# main.net
KiCad netlist of a schematic drawn in Altium Designer
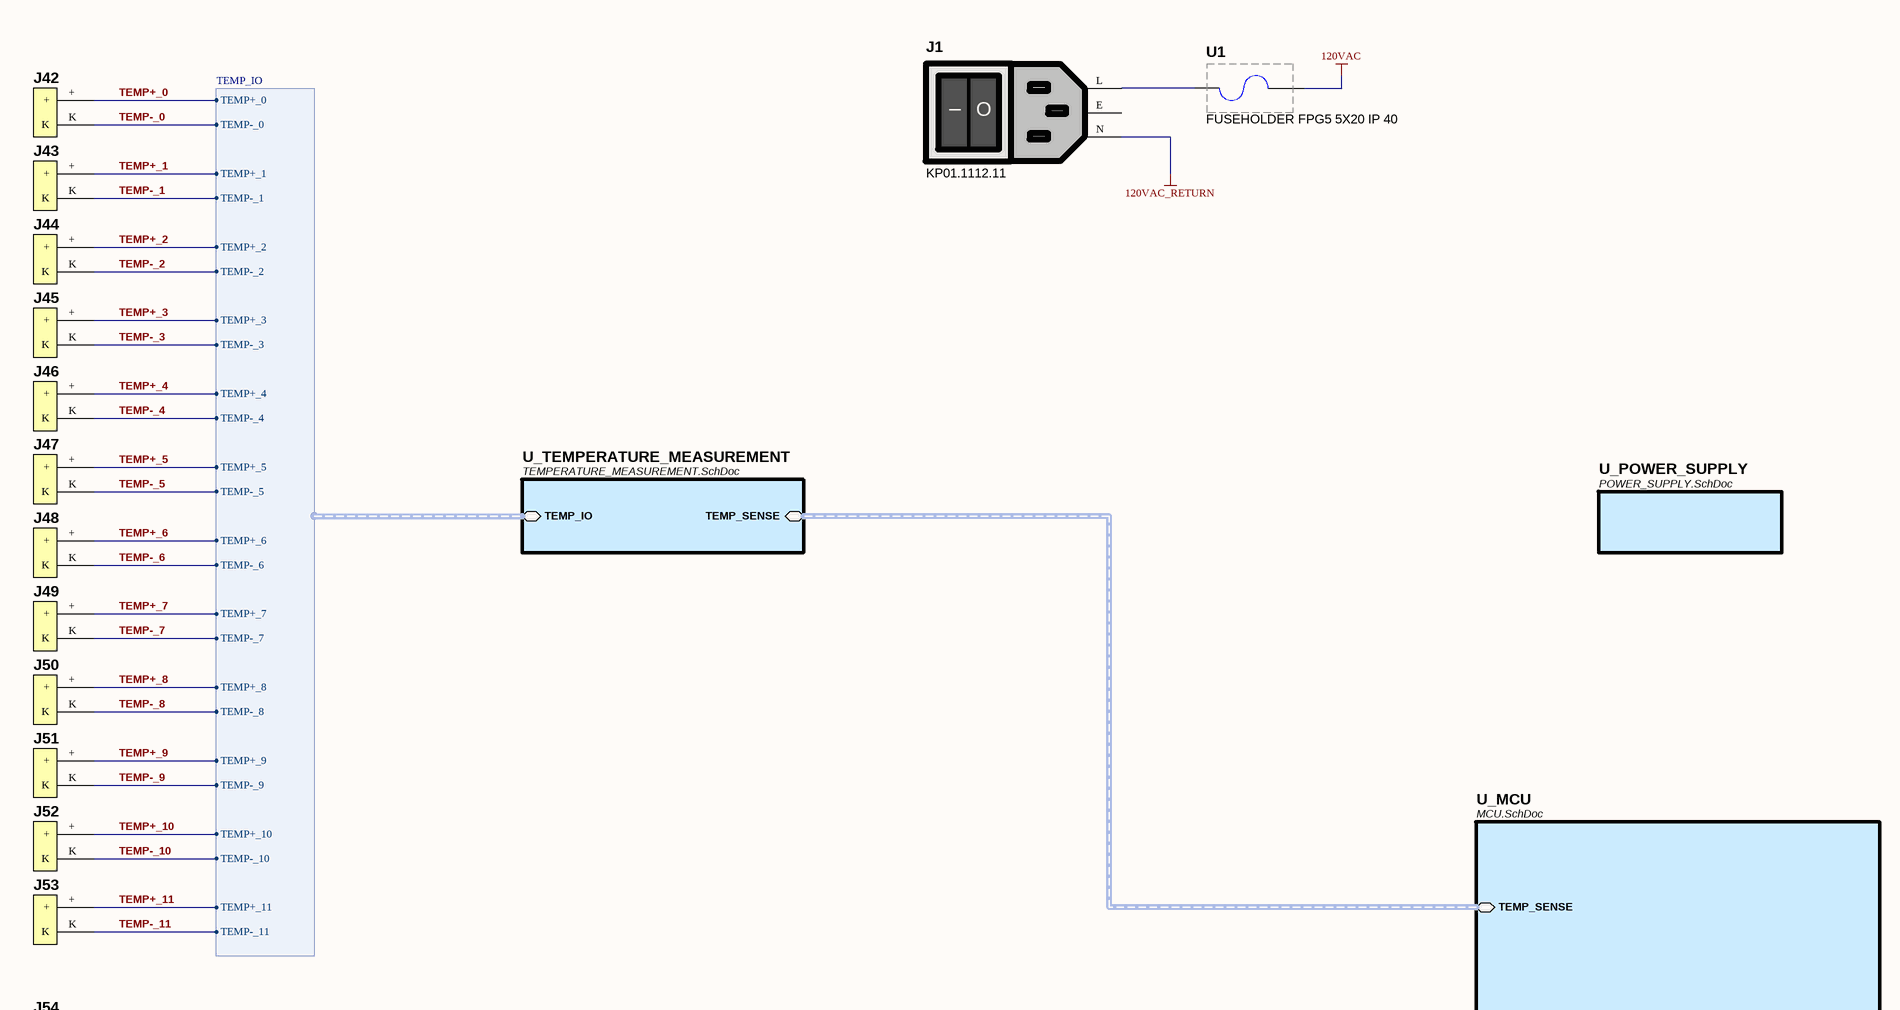
[diagram p0: main.SchDoc, top left]
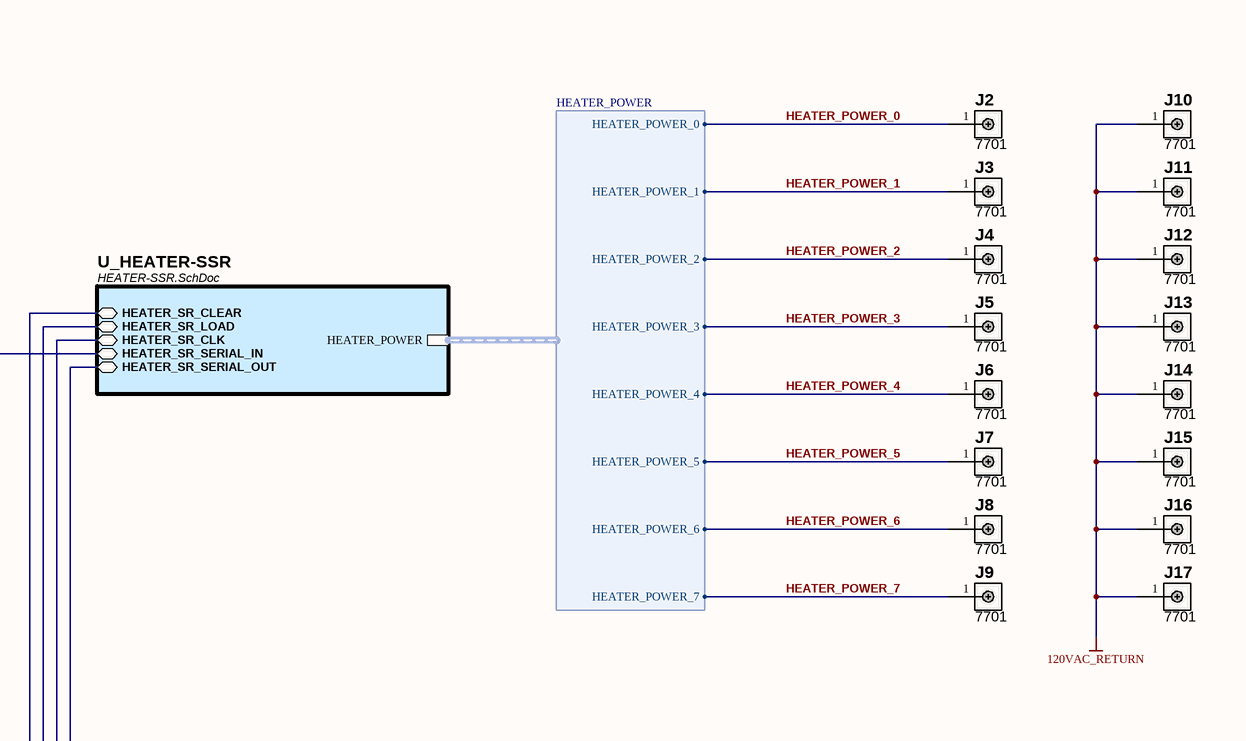
[diagram p1: main.SchDoc, top right]
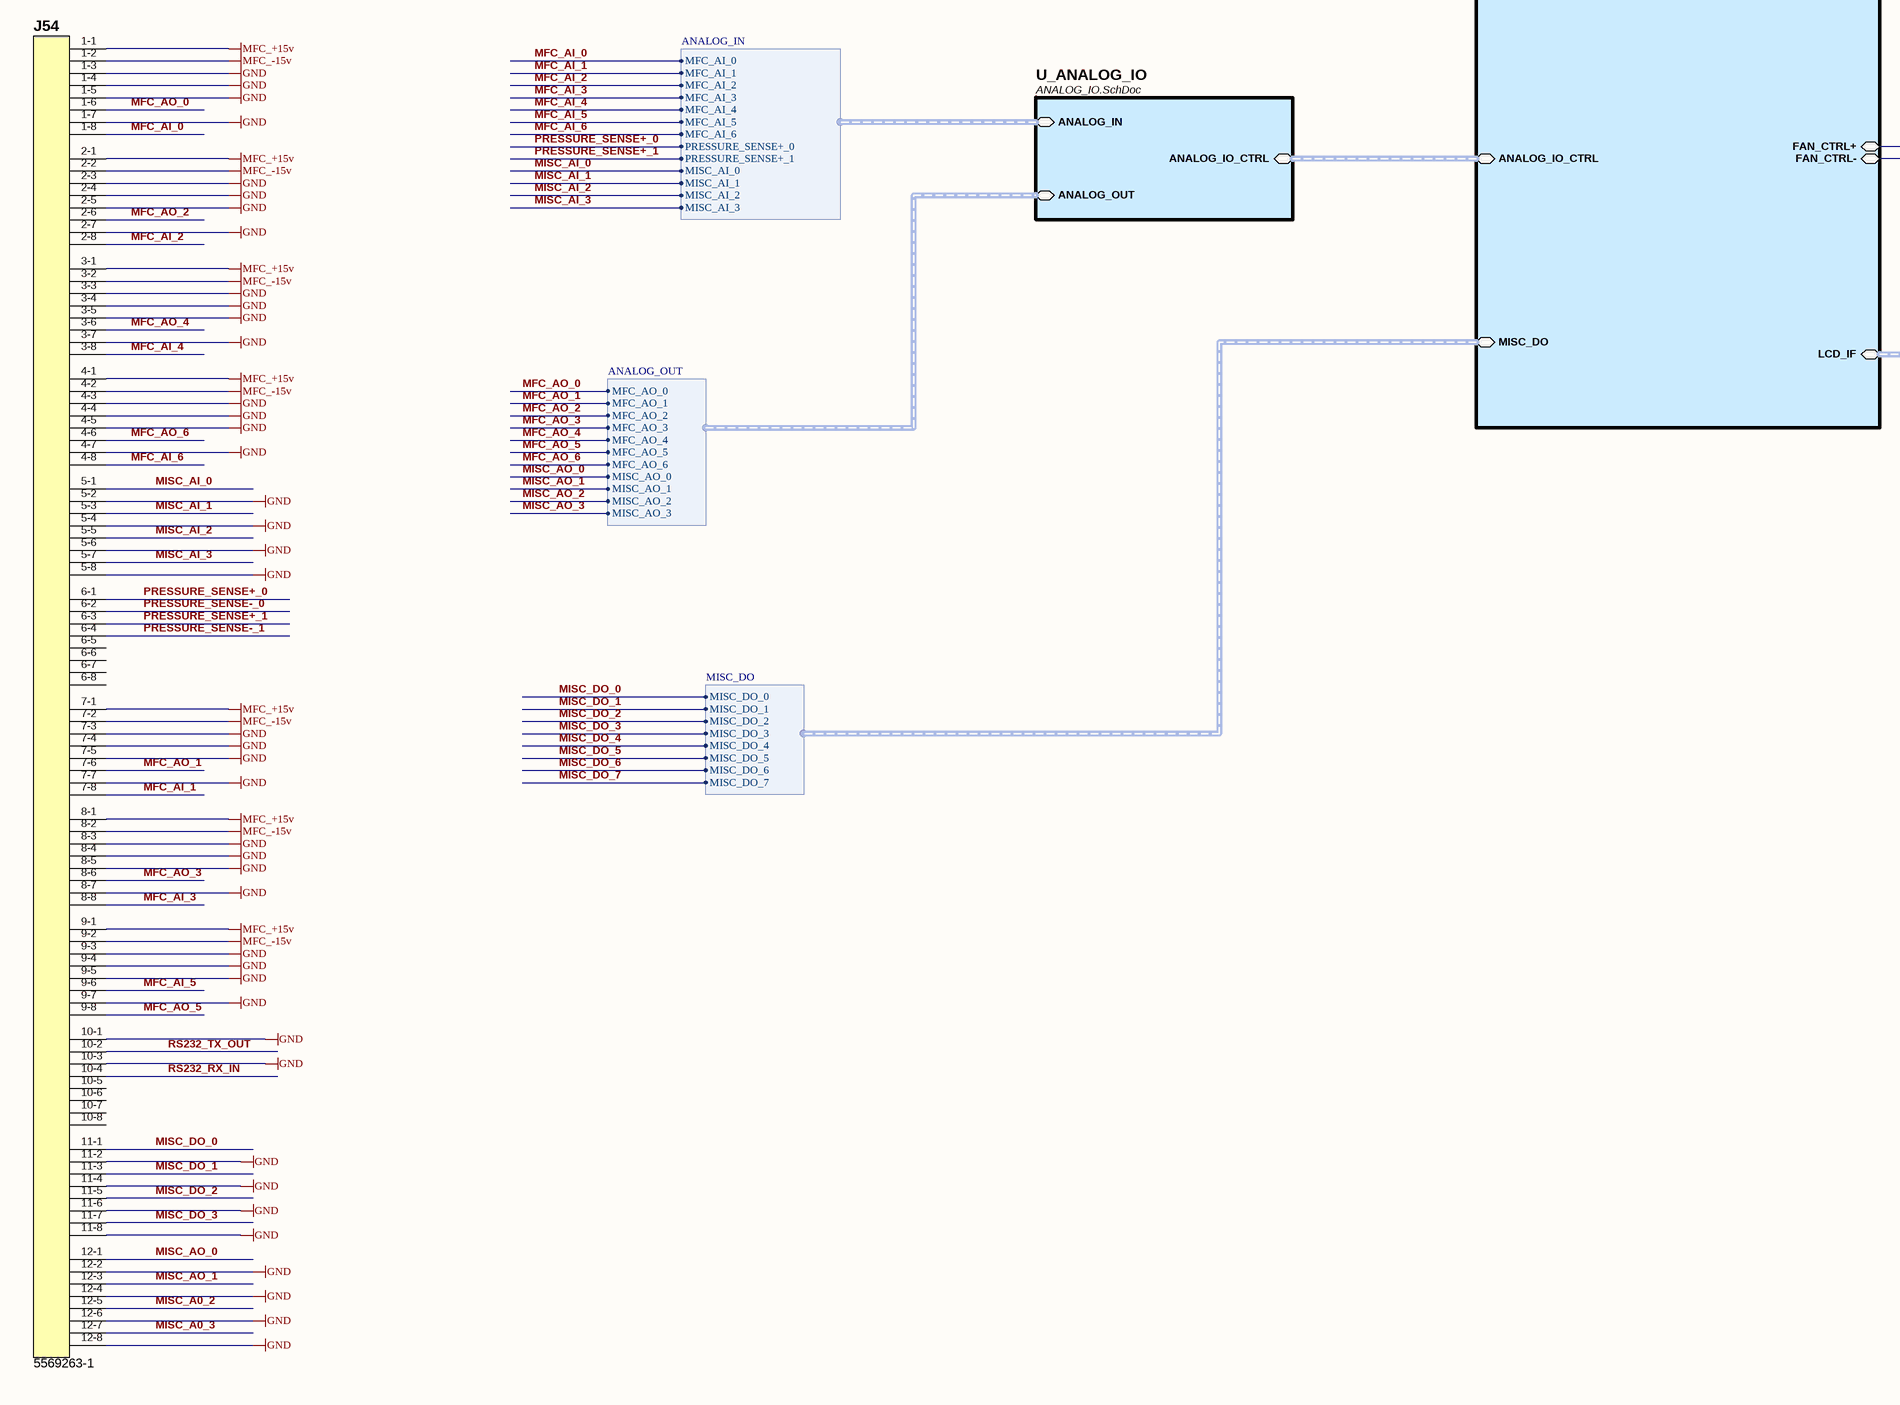
[diagram p2: main.SchDoc, bottom left]
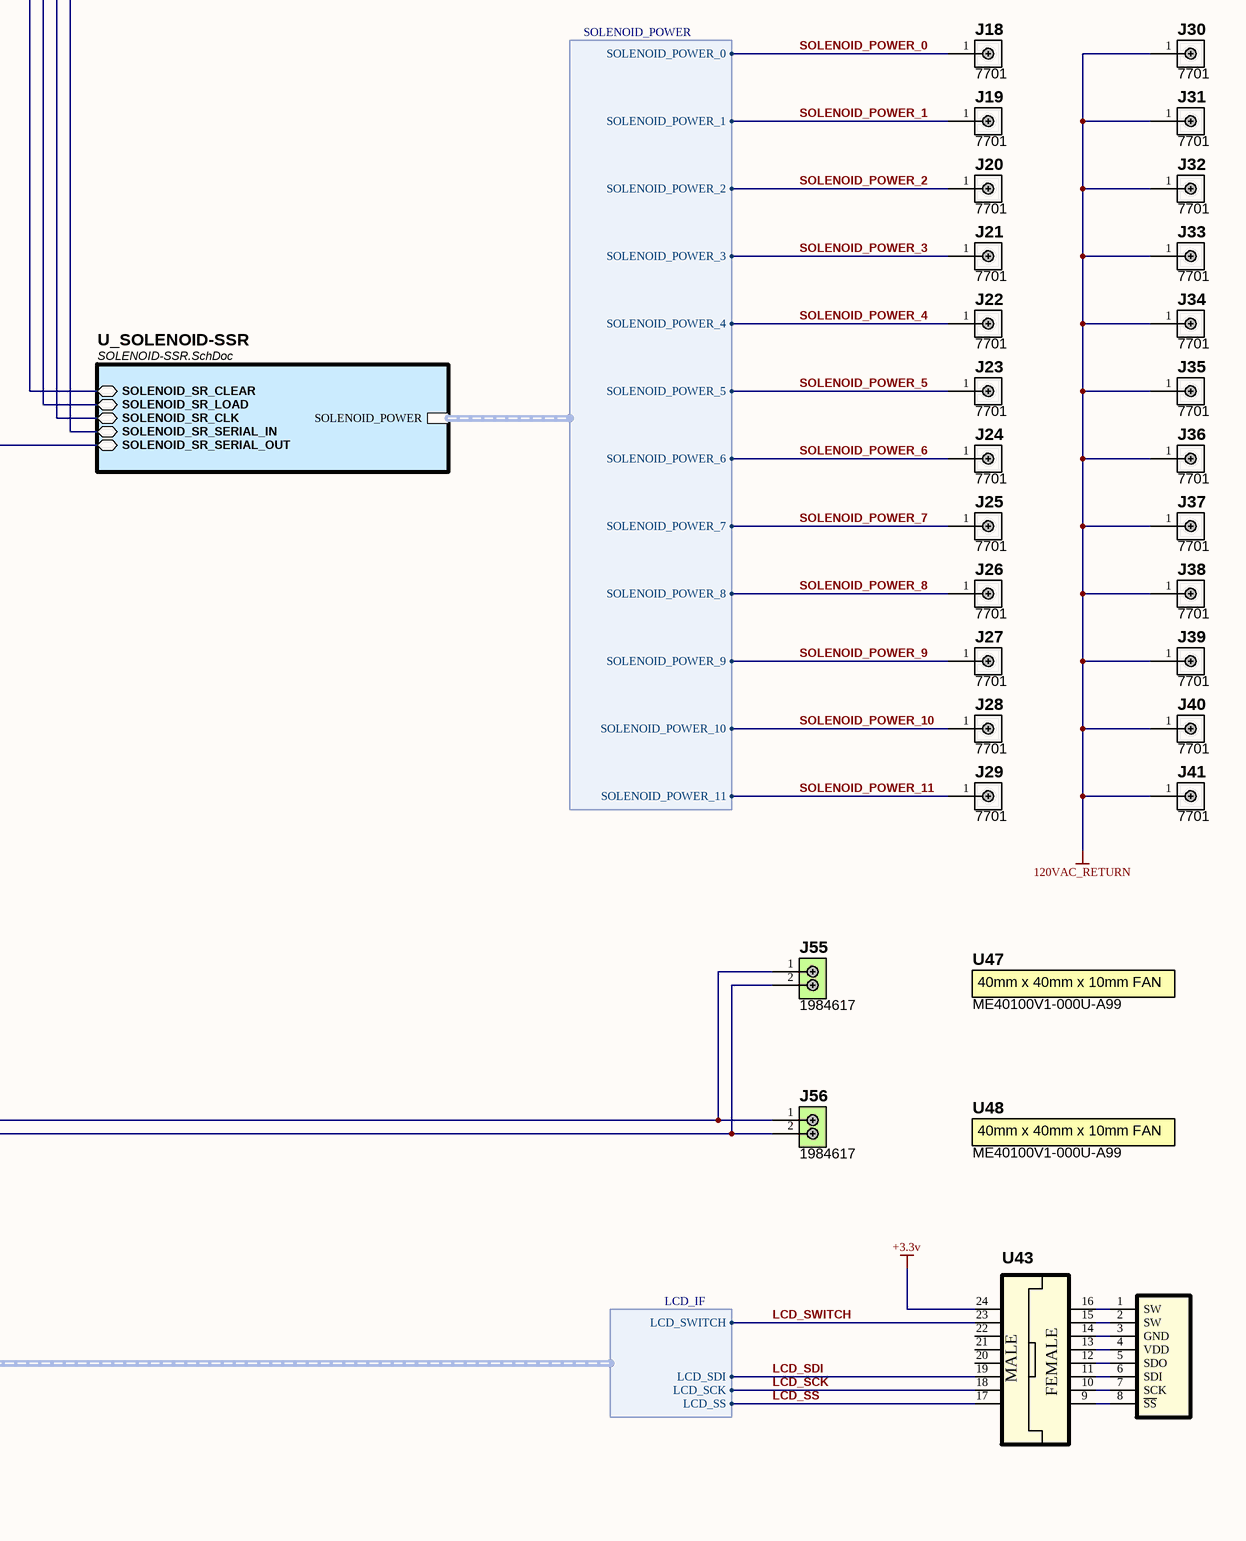
[diagram p3: main.SchDoc, bottom right]

(export (version "E")
  (design (tool "Eeschema 10.0.6"))
  (components
    (comp (ref "J1")
      (value "KP01.1112.11")
      (footprint "KP01.1112.11")
      (description "AC Power Entry Modules SNAP-N PCB 2-POLE")
      (fields (field (name "MANUFACTURER") "Schurter"))
      (libsource (lib "eModule") (part "KP01.1112.11"))
    )
    (comp (ref "J2")
      (value "7701")
      (footprint "7701")
      (description "TERM W/ASSEMBLD SCREW VERT PCMNT")
      (fields (field (name "MANUFACTURER") "Keystone Electronics"))
      (libsource (lib "eConnector") (part "7701"))
    )
    (comp (ref "J3")
      (value "7701")
      (footprint "7701")
      (description "TERM W/ASSEMBLD SCREW VERT PCMNT")
      (fields (field (name "MANUFACTURER") "Keystone Electronics"))
      (libsource (lib "eConnector") (part "7701"))
    )
    (comp (ref "J4")
      (value "7701")
      (footprint "7701")
      (description "TERM W/ASSEMBLD SCREW VERT PCMNT")
      (fields (field (name "MANUFACTURER") "Keystone Electronics"))
      (libsource (lib "eConnector") (part "7701"))
    )
    (comp (ref "J5")
      (value "7701")
      (footprint "7701")
      (description "TERM W/ASSEMBLD SCREW VERT PCMNT")
      (fields (field (name "MANUFACTURER") "Keystone Electronics"))
      (libsource (lib "eConnector") (part "7701"))
    )
    (comp (ref "J6")
      (value "7701")
      (footprint "7701")
      (description "TERM W/ASSEMBLD SCREW VERT PCMNT")
      (fields (field (name "MANUFACTURER") "Keystone Electronics"))
      (libsource (lib "eConnector") (part "7701"))
    )
    (comp (ref "J7")
      (value "7701")
      (footprint "7701")
      (description "TERM W/ASSEMBLD SCREW VERT PCMNT")
      (fields (field (name "MANUFACTURER") "Keystone Electronics"))
      (libsource (lib "eConnector") (part "7701"))
    )
    (comp (ref "J8")
      (value "7701")
      (footprint "7701")
      (description "TERM W/ASSEMBLD SCREW VERT PCMNT")
      (fields (field (name "MANUFACTURER") "Keystone Electronics"))
      (libsource (lib "eConnector") (part "7701"))
    )
    (comp (ref "J9")
      (value "7701")
      (footprint "7701")
      (description "TERM W/ASSEMBLD SCREW VERT PCMNT")
      (fields (field (name "MANUFACTURER") "Keystone Electronics"))
      (libsource (lib "eConnector") (part "7701"))
    )
    (comp (ref "J10")
      (value "7701")
      (footprint "7701")
      (description "TERM W/ASSEMBLD SCREW VERT PCMNT")
      (fields (field (name "MANUFACTURER") "Keystone Electronics"))
      (libsource (lib "eConnector") (part "7701"))
    )
    (comp (ref "J11")
      (value "7701")
      (footprint "7701")
      (description "TERM W/ASSEMBLD SCREW VERT PCMNT")
      (fields (field (name "MANUFACTURER") "Keystone Electronics"))
      (libsource (lib "eConnector") (part "7701"))
    )
    (comp (ref "J12")
      (value "7701")
      (footprint "7701")
      (description "TERM W/ASSEMBLD SCREW VERT PCMNT")
      (fields (field (name "MANUFACTURER") "Keystone Electronics"))
      (libsource (lib "eConnector") (part "7701"))
    )
    (comp (ref "J13")
      (value "7701")
      (footprint "7701")
      (description "TERM W/ASSEMBLD SCREW VERT PCMNT")
      (fields (field (name "MANUFACTURER") "Keystone Electronics"))
      (libsource (lib "eConnector") (part "7701"))
    )
    (comp (ref "J14")
      (value "7701")
      (footprint "7701")
      (description "TERM W/ASSEMBLD SCREW VERT PCMNT")
      (fields (field (name "MANUFACTURER") "Keystone Electronics"))
      (libsource (lib "eConnector") (part "7701"))
    )
    (comp (ref "J15")
      (value "7701")
      (footprint "7701")
      (description "TERM W/ASSEMBLD SCREW VERT PCMNT")
      (fields (field (name "MANUFACTURER") "Keystone Electronics"))
      (libsource (lib "eConnector") (part "7701"))
    )
    (comp (ref "J16")
      (value "7701")
      (footprint "7701")
      (description "TERM W/ASSEMBLD SCREW VERT PCMNT")
      (fields (field (name "MANUFACTURER") "Keystone Electronics"))
      (libsource (lib "eConnector") (part "7701"))
    )
    (comp (ref "J17")
      (value "7701")
      (footprint "7701")
      (description "TERM W/ASSEMBLD SCREW VERT PCMNT")
      (fields (field (name "MANUFACTURER") "Keystone Electronics"))
      (libsource (lib "eConnector") (part "7701"))
    )
    (comp (ref "J18")
      (value "7701")
      (footprint "7701")
      (description "TERM W/ASSEMBLD SCREW VERT PCMNT")
      (fields (field (name "MANUFACTURER") "Keystone Electronics"))
      (libsource (lib "eConnector") (part "7701"))
    )
    (comp (ref "J19")
      (value "7701")
      (footprint "7701")
      (description "TERM W/ASSEMBLD SCREW VERT PCMNT")
      (fields (field (name "MANUFACTURER") "Keystone Electronics"))
      (libsource (lib "eConnector") (part "7701"))
    )
    (comp (ref "J20")
      (value "7701")
      (footprint "7701")
      (description "TERM W/ASSEMBLD SCREW VERT PCMNT")
      (fields (field (name "MANUFACTURER") "Keystone Electronics"))
      (libsource (lib "eConnector") (part "7701"))
    )
    (comp (ref "J21")
      (value "7701")
      (footprint "7701")
      (description "TERM W/ASSEMBLD SCREW VERT PCMNT")
      (fields (field (name "MANUFACTURER") "Keystone Electronics"))
      (libsource (lib "eConnector") (part "7701"))
    )
    (comp (ref "J22")
      (value "7701")
      (footprint "7701")
      (description "TERM W/ASSEMBLD SCREW VERT PCMNT")
      (fields (field (name "MANUFACTURER") "Keystone Electronics"))
      (libsource (lib "eConnector") (part "7701"))
    )
    (comp (ref "J23")
      (value "7701")
      (footprint "7701")
      (description "TERM W/ASSEMBLD SCREW VERT PCMNT")
      (fields (field (name "MANUFACTURER") "Keystone Electronics"))
      (libsource (lib "eConnector") (part "7701"))
    )
    (comp (ref "J24")
      (value "7701")
      (footprint "7701")
      (description "TERM W/ASSEMBLD SCREW VERT PCMNT")
      (fields (field (name "MANUFACTURER") "Keystone Electronics"))
      (libsource (lib "eConnector") (part "7701"))
    )
    (comp (ref "J25")
      (value "7701")
      (footprint "7701")
      (description "TERM W/ASSEMBLD SCREW VERT PCMNT")
      (fields (field (name "MANUFACTURER") "Keystone Electronics"))
      (libsource (lib "eConnector") (part "7701"))
    )
    (comp (ref "J26")
      (value "7701")
      (footprint "7701")
      (description "TERM W/ASSEMBLD SCREW VERT PCMNT")
      (fields (field (name "MANUFACTURER") "Keystone Electronics"))
      (libsource (lib "eConnector") (part "7701"))
    )
    (comp (ref "J27")
      (value "7701")
      (footprint "7701")
      (description "TERM W/ASSEMBLD SCREW VERT PCMNT")
      (fields (field (name "MANUFACTURER") "Keystone Electronics"))
      (libsource (lib "eConnector") (part "7701"))
    )
    (comp (ref "J28")
      (value "7701")
      (footprint "7701")
      (description "TERM W/ASSEMBLD SCREW VERT PCMNT")
      (fields (field (name "MANUFACTURER") "Keystone Electronics"))
      (libsource (lib "eConnector") (part "7701"))
    )
    (comp (ref "J29")
      (value "7701")
      (footprint "7701")
      (description "TERM W/ASSEMBLD SCREW VERT PCMNT")
      (fields (field (name "MANUFACTURER") "Keystone Electronics"))
      (libsource (lib "eConnector") (part "7701"))
    )
    (comp (ref "J30")
      (value "7701")
      (footprint "7701")
      (description "TERM W/ASSEMBLD SCREW VERT PCMNT")
      (fields (field (name "MANUFACTURER") "Keystone Electronics"))
      (libsource (lib "eConnector") (part "7701"))
    )
    (comp (ref "J31")
      (value "7701")
      (footprint "7701")
      (description "TERM W/ASSEMBLD SCREW VERT PCMNT")
      (fields (field (name "MANUFACTURER") "Keystone Electronics"))
      (libsource (lib "eConnector") (part "7701"))
    )
    (comp (ref "J32")
      (value "7701")
      (footprint "7701")
      (description "TERM W/ASSEMBLD SCREW VERT PCMNT")
      (fields (field (name "MANUFACTURER") "Keystone Electronics"))
      (libsource (lib "eConnector") (part "7701"))
    )
    (comp (ref "J33")
      (value "7701")
      (footprint "7701")
      (description "TERM W/ASSEMBLD SCREW VERT PCMNT")
      (fields (field (name "MANUFACTURER") "Keystone Electronics"))
      (libsource (lib "eConnector") (part "7701"))
    )
    (comp (ref "J34")
      (value "7701")
      (footprint "7701")
      (description "TERM W/ASSEMBLD SCREW VERT PCMNT")
      (fields (field (name "MANUFACTURER") "Keystone Electronics"))
      (libsource (lib "eConnector") (part "7701"))
    )
    (comp (ref "J35")
      (value "7701")
      (footprint "7701")
      (description "TERM W/ASSEMBLD SCREW VERT PCMNT")
      (fields (field (name "MANUFACTURER") "Keystone Electronics"))
      (libsource (lib "eConnector") (part "7701"))
    )
    (comp (ref "J36")
      (value "7701")
      (footprint "7701")
      (description "TERM W/ASSEMBLD SCREW VERT PCMNT")
      (fields (field (name "MANUFACTURER") "Keystone Electronics"))
      (libsource (lib "eConnector") (part "7701"))
    )
    (comp (ref "J37")
      (value "7701")
      (footprint "7701")
      (description "TERM W/ASSEMBLD SCREW VERT PCMNT")
      (fields (field (name "MANUFACTURER") "Keystone Electronics"))
      (libsource (lib "eConnector") (part "7701"))
    )
    (comp (ref "J38")
      (value "7701")
      (footprint "7701")
      (description "TERM W/ASSEMBLD SCREW VERT PCMNT")
      (fields (field (name "MANUFACTURER") "Keystone Electronics"))
      (libsource (lib "eConnector") (part "7701"))
    )
    (comp (ref "J39")
      (value "7701")
      (footprint "7701")
      (description "TERM W/ASSEMBLD SCREW VERT PCMNT")
      (fields (field (name "MANUFACTURER") "Keystone Electronics"))
      (libsource (lib "eConnector") (part "7701"))
    )
    (comp (ref "J40")
      (value "7701")
      (footprint "7701")
      (description "TERM W/ASSEMBLD SCREW VERT PCMNT")
      (fields (field (name "MANUFACTURER") "Keystone Electronics"))
      (libsource (lib "eConnector") (part "7701"))
    )
    (comp (ref "J41")
      (value "7701")
      (footprint "7701")
      (description "TERM W/ASSEMBLD SCREW VERT PCMNT")
      (fields (field (name "MANUFACTURER") "Keystone Electronics"))
      (libsource (lib "eConnector") (part "7701"))
    )
    (comp (ref "J42")
      (value "PCC-SMP-K")
      (footprint "PCC-SMP-V")
      (description "Vertical K type thermocouple connector - K")
      (fields (field (name "MANUFACTURER") "Omega"))
      (libsource (lib "eConnector") (part "PCC-SMP-K-100"))
    )
    (comp (ref "J43")
      (value "PCC-SMP-K")
      (footprint "PCC-SMP-V")
      (description "Vertical K type thermocouple connector - K")
      (fields (field (name "MANUFACTURER") "Omega"))
      (libsource (lib "eConnector") (part "PCC-SMP-K-100"))
    )
    (comp (ref "J44")
      (value "PCC-SMP-K")
      (footprint "PCC-SMP-V")
      (description "Vertical K type thermocouple connector - K")
      (fields (field (name "MANUFACTURER") "Omega"))
      (libsource (lib "eConnector") (part "PCC-SMP-K-100"))
    )
    (comp (ref "J45")
      (value "PCC-SMP-K")
      (footprint "PCC-SMP-V")
      (description "Vertical K type thermocouple connector - K")
      (fields (field (name "MANUFACTURER") "Omega"))
      (libsource (lib "eConnector") (part "PCC-SMP-K-100"))
    )
    (comp (ref "J46")
      (value "PCC-SMP-K")
      (footprint "PCC-SMP-V")
      (description "Vertical K type thermocouple connector - K")
      (fields (field (name "MANUFACTURER") "Omega"))
      (libsource (lib "eConnector") (part "PCC-SMP-K-100"))
    )
    (comp (ref "J47")
      (value "PCC-SMP-K")
      (footprint "PCC-SMP-V")
      (description "Vertical K type thermocouple connector - K")
      (fields (field (name "MANUFACTURER") "Omega"))
      (libsource (lib "eConnector") (part "PCC-SMP-K-100"))
    )
    (comp (ref "J48")
      (value "PCC-SMP-K")
      (footprint "PCC-SMP-V")
      (description "Vertical K type thermocouple connector - K")
      (fields (field (name "MANUFACTURER") "Omega"))
      (libsource (lib "eConnector") (part "PCC-SMP-K-100"))
    )
    (comp (ref "J49")
      (value "PCC-SMP-K")
      (footprint "PCC-SMP-V")
      (description "Vertical K type thermocouple connector - K")
      (fields (field (name "MANUFACTURER") "Omega"))
      (libsource (lib "eConnector") (part "PCC-SMP-K-100"))
    )
    (comp (ref "J50")
      (value "PCC-SMP-K")
      (footprint "PCC-SMP-V")
      (description "Vertical K type thermocouple connector - K")
      (fields (field (name "MANUFACTURER") "Omega"))
      (libsource (lib "eConnector") (part "PCC-SMP-K-100"))
    )
    (comp (ref "J51")
      (value "PCC-SMP-K")
      (footprint "PCC-SMP-V")
      (description "Vertical K type thermocouple connector - K")
      (fields (field (name "MANUFACTURER") "Omega"))
      (libsource (lib "eConnector") (part "PCC-SMP-K-100"))
    )
    (comp (ref "J52")
      (value "PCC-SMP-K")
      (footprint "PCC-SMP-V")
      (description "Vertical K type thermocouple connector - K")
      (fields (field (name "MANUFACTURER") "Omega"))
      (libsource (lib "eConnector") (part "PCC-SMP-K-100"))
    )
    (comp (ref "J53")
      (value "PCC-SMP-K")
      (footprint "PCC-SMP-V")
      (description "Vertical K type thermocouple connector - K")
      (fields (field (name "MANUFACTURER") "Omega"))
      (libsource (lib "eConnector") (part "PCC-SMP-K-100"))
    )
    (comp (ref "J54")
      (value "5569263-1")
      (footprint "5569263-1")
      (description "CONN MOD JACK R/A 8P8C SHIELDED")
      (fields (field (name "MANUFACTURER") "TE Connectivity"))
      (libsource (lib "eConnector") (part "5569263-1"))
    )
    (comp (ref "J55")
      (value "1984617")
      (footprint "1984617")
      (description "CONN TERM BLOCK T/H 2POS 3.5MM")
      (fields (field (name "MANUFACTURER") "Phoenix Contact") (field (name "VOLTAGE") "300V"))
      (libsource (lib "eConnector") (part "1984617"))
    )
    (comp (ref "J56")
      (value "1984617")
      (footprint "1984617")
      (description "CONN TERM BLOCK T/H 2POS 3.5MM")
      (fields (field (name "MANUFACTURER") "Phoenix Contact") (field (name "VOLTAGE") "300V"))
      (libsource (lib "eConnector") (part "1984617"))
    )
    (comp (ref "U1")
      (value "FUSEHOLDER FPG5 5X20 IP 40")
      (footprint "3101.0055")
      (fields
        (field (name "MANUFACTURER") "Schurter Inc")
        (field (name "MANUFACTURER PART NUMBER") "3101.0055")
        (field (name "VOLTAGE") "250V")
      )
      (libsource (lib "eElectroMechanical") (part "3101.0055"))
    )
    (comp (ref "U43")
      (value "IS15DSBFP4RGB")
      (footprint "R/A IS15DSBFP4RGB")
      (description "64x32 Compact Smart Switch")
      (fields (field (name "MANUFACTURER") "NKK Switches"))
      (libsource (lib "eModule") (part "R/A IS15DSBFP4RGB"))
    )
    (comp (ref "U47")
      (value "ME40100V1-000U-A99")
      (footprint "ME40100V1-000U-A99")
      (description "FAN 40X10MM 5VDC 1.08W 8CFM")
      (fields (field (name "MANUFACTURER") "Sunon Fans"))
      (libsource (lib "eElectroMechanical") (part "ME40100V1-000U-A99"))
    )
    (comp (ref "U48")
      (value "ME40100V1-000U-A99")
      (footprint "ME40100V1-000U-A99")
      (description "FAN 40X10MM 5VDC 1.08W 8CFM")
      (fields (field (name "MANUFACTURER") "Sunon Fans"))
      (libsource (lib "eElectroMechanical") (part "ME40100V1-000U-A99"))
    )
  )
  (nets
    (net (code "8") (name "+3.3v") (class "Default")
      (node (ref "U43") (pin "24") (pinfunction "24_24") (pintype "passive"))
    )
    (net (code "10") (name "/FAN_CTRL+") (class "Default")
      (node (ref "J55") (pin "1") (pinfunction "1_1") (pintype "passive"))
      (node (ref "J56") (pin "1") (pinfunction "1_1") (pintype "passive"))
    )
    (net (code "11") (name "/FAN_CTRL-") (class "Default")
      (node (ref "J55") (pin "2") (pinfunction "2_2") (pintype "passive"))
      (node (ref "J56") (pin "2") (pinfunction "2_2") (pintype "passive"))
    )
    (net (code "12") (name "/HEATER_POWER_0") (class "Default")
      (node (ref "J2") (pin "1") (pinfunction "1_1") (pintype "passive"))
    )
    (net (code "13") (name "/HEATER_POWER_1") (class "Default")
      (node (ref "J3") (pin "1") (pinfunction "1_1") (pintype "passive"))
    )
    (net (code "14") (name "/HEATER_POWER_2") (class "Default")
      (node (ref "J4") (pin "1") (pinfunction "1_1") (pintype "passive"))
    )
    (net (code "15") (name "/HEATER_POWER_3") (class "Default")
      (node (ref "J5") (pin "1") (pinfunction "1_1") (pintype "passive"))
    )
    (net (code "16") (name "/HEATER_POWER_4") (class "Default")
      (node (ref "J6") (pin "1") (pinfunction "1_1") (pintype "passive"))
    )
    (net (code "17") (name "/HEATER_POWER_5") (class "Default")
      (node (ref "J7") (pin "1") (pinfunction "1_1") (pintype "passive"))
    )
    (net (code "18") (name "/HEATER_POWER_6") (class "Default")
      (node (ref "J8") (pin "1") (pinfunction "1_1") (pintype "passive"))
    )
    (net (code "19") (name "/HEATER_POWER_7") (class "Default")
      (node (ref "J9") (pin "1") (pinfunction "1_1") (pintype "passive"))
    )
    (net (code "25") (name "/LCD_SCK") (class "Default")
      (node (ref "U43") (pin "18") (pinfunction "18_18") (pintype "passive"))
    )
    (net (code "26") (name "/LCD_SDI") (class "Default")
      (node (ref "U43") (pin "19") (pinfunction "19_19") (pintype "passive"))
    )
    (net (code "27") (name "/LCD_SS") (class "Default")
      (node (ref "U43") (pin "17") (pinfunction "17_17") (pintype "passive"))
    )
    (net (code "28") (name "/LCD_SWITCH") (class "Default")
      (node (ref "U43") (pin "23") (pinfunction "23_23") (pintype "passive"))
    )
    (net (code "29") (name "/MFC_AI_0") (class "Default")
      (node (ref "J54") (pin "1-8") (pinfunction "1-8_1-8") (pintype "passive"))
    )
    (net (code "30") (name "/MFC_AI_1") (class "Default")
      (node (ref "J54") (pin "7-8") (pinfunction "7-8_7-8") (pintype "passive"))
    )
    (net (code "31") (name "/MFC_AI_2") (class "Default")
      (node (ref "J54") (pin "2-8") (pinfunction "2-8_2-8") (pintype "passive"))
    )
    (net (code "32") (name "/MFC_AI_3") (class "Default")
      (node (ref "J54") (pin "8-8") (pinfunction "8-8_8-8") (pintype "passive"))
    )
    (net (code "33") (name "/MFC_AI_4") (class "Default")
      (node (ref "J54") (pin "3-8") (pinfunction "3-8_3-8") (pintype "passive"))
    )
    (net (code "34") (name "/MFC_AI_5") (class "Default")
      (node (ref "J54") (pin "9-6") (pinfunction "9-6_9-6") (pintype "passive"))
    )
    (net (code "35") (name "/MFC_AI_6") (class "Default")
      (node (ref "J54") (pin "4-8") (pinfunction "4-8_4-8") (pintype "passive"))
    )
    (net (code "36") (name "/MFC_AO_0") (class "Default")
      (node (ref "J54") (pin "1-6") (pinfunction "1-6_1-6") (pintype "passive"))
    )
    (net (code "37") (name "/MFC_AO_1") (class "Default")
      (node (ref "J54") (pin "7-6") (pinfunction "7-6_7-6") (pintype "passive"))
    )
    (net (code "38") (name "/MFC_AO_2") (class "Default")
      (node (ref "J54") (pin "2-6") (pinfunction "2-6_2-6") (pintype "passive"))
    )
    (net (code "39") (name "/MFC_AO_3") (class "Default")
      (node (ref "J54") (pin "8-6") (pinfunction "8-6_8-6") (pintype "passive"))
    )
    (net (code "40") (name "/MFC_AO_4") (class "Default")
      (node (ref "J54") (pin "3-6") (pinfunction "3-6_3-6") (pintype "passive"))
    )
    (net (code "41") (name "/MFC_AO_5") (class "Default")
      (node (ref "J54") (pin "9-8") (pinfunction "9-8_9-8") (pintype "passive"))
    )
    (net (code "42") (name "/MFC_AO_6") (class "Default")
      (node (ref "J54") (pin "4-6") (pinfunction "4-6_4-6") (pintype "passive"))
    )
    (net (code "43") (name "/MISC_A0_2") (class "Default")
      (node (ref "J54") (pin "12-5") (pinfunction "12-5_12-5") (pintype "passive"))
    )
    (net (code "44") (name "/MISC_A0_3") (class "Default")
      (node (ref "J54") (pin "12-7") (pinfunction "12-7_12-7") (pintype "passive"))
    )
    (net (code "45") (name "/MISC_AI_0") (class "Default")
      (node (ref "J54") (pin "5-1") (pinfunction "5-1_5-1") (pintype "passive"))
    )
    (net (code "46") (name "/MISC_AI_1") (class "Default")
      (node (ref "J54") (pin "5-3") (pinfunction "5-3_5-3") (pintype "passive"))
    )
    (net (code "47") (name "/MISC_AI_2") (class "Default")
      (node (ref "J54") (pin "5-5") (pinfunction "5-5_5-5") (pintype "passive"))
    )
    (net (code "48") (name "/MISC_AI_3") (class "Default")
      (node (ref "J54") (pin "5-7") (pinfunction "5-7_5-7") (pintype "passive"))
    )
    (net (code "49") (name "/MISC_AO_0") (class "Default")
      (node (ref "J54") (pin "12-1") (pinfunction "12-1_12-1") (pintype "passive"))
    )
    (net (code "50") (name "/MISC_AO_1") (class "Default")
      (node (ref "J54") (pin "12-3") (pinfunction "12-3_12-3") (pintype "passive"))
    )
    (net (code "53") (name "/MISC_DO_0") (class "Default")
      (node (ref "J54") (pin "11-1") (pinfunction "11-1_11-1") (pintype "passive"))
    )
    (net (code "54") (name "/MISC_DO_1") (class "Default")
      (node (ref "J54") (pin "11-3") (pinfunction "11-3_11-3") (pintype "passive"))
    )
    (net (code "55") (name "/MISC_DO_2") (class "Default")
      (node (ref "J54") (pin "11-5") (pinfunction "11-5_11-5") (pintype "passive"))
    )
    (net (code "56") (name "/MISC_DO_3") (class "Default")
      (node (ref "J54") (pin "11-7") (pinfunction "11-7_11-7") (pintype "passive"))
    )
    (net (code "61") (name "/PRESSURE_SENSE+_0") (class "Default")
      (node (ref "J54") (pin "6-1") (pinfunction "6-1_6-1") (pintype "passive"))
    )
    (net (code "62") (name "/PRESSURE_SENSE+_1") (class "Default")
      (node (ref "J54") (pin "6-3") (pinfunction "6-3_6-3") (pintype "passive"))
    )
    (net (code "63") (name "/PRESSURE_SENSE-_0") (class "Default")
      (node (ref "J54") (pin "6-2") (pinfunction "6-2_6-2") (pintype "passive"))
    )
    (net (code "64") (name "/PRESSURE_SENSE-_1") (class "Default")
      (node (ref "J54") (pin "6-4") (pinfunction "6-4_6-4") (pintype "passive"))
    )
    (net (code "65") (name "/RS232_RX_IN") (class "Default")
      (node (ref "J54") (pin "10-4") (pinfunction "10-4_10-4") (pintype "passive"))
    )
    (net (code "66") (name "/RS232_TX_OUT") (class "Default")
      (node (ref "J54") (pin "10-2") (pinfunction "10-2_10-2") (pintype "passive"))
    )
    (net (code "67") (name "/SOLENOID_POWER_0") (class "Default")
      (node (ref "J18") (pin "1") (pinfunction "1_1") (pintype "passive"))
    )
    (net (code "68") (name "/SOLENOID_POWER_1") (class "Default")
      (node (ref "J19") (pin "1") (pinfunction "1_1") (pintype "passive"))
    )
    (net (code "69") (name "/SOLENOID_POWER_2") (class "Default")
      (node (ref "J20") (pin "1") (pinfunction "1_1") (pintype "passive"))
    )
    (net (code "70") (name "/SOLENOID_POWER_3") (class "Default")
      (node (ref "J21") (pin "1") (pinfunction "1_1") (pintype "passive"))
    )
    (net (code "71") (name "/SOLENOID_POWER_4") (class "Default")
      (node (ref "J22") (pin "1") (pinfunction "1_1") (pintype "passive"))
    )
    (net (code "72") (name "/SOLENOID_POWER_5") (class "Default")
      (node (ref "J23") (pin "1") (pinfunction "1_1") (pintype "passive"))
    )
    (net (code "73") (name "/SOLENOID_POWER_6") (class "Default")
      (node (ref "J24") (pin "1") (pinfunction "1_1") (pintype "passive"))
    )
    (net (code "74") (name "/SOLENOID_POWER_7") (class "Default")
      (node (ref "J25") (pin "1") (pinfunction "1_1") (pintype "passive"))
    )
    (net (code "75") (name "/SOLENOID_POWER_8") (class "Default")
      (node (ref "J26") (pin "1") (pinfunction "1_1") (pintype "passive"))
    )
    (net (code "76") (name "/SOLENOID_POWER_9") (class "Default")
      (node (ref "J27") (pin "1") (pinfunction "1_1") (pintype "passive"))
    )
    (net (code "77") (name "/SOLENOID_POWER_10") (class "Default")
      (node (ref "J28") (pin "1") (pinfunction "1_1") (pintype "passive"))
    )
    (net (code "78") (name "/SOLENOID_POWER_11") (class "Default")
      (node (ref "J29") (pin "1") (pinfunction "1_1") (pintype "passive"))
    )
    (net (code "80") (name "/TEMP+_0") (class "Default")
      (node (ref "J42") (pin "+") (pinfunction "+_+") (pintype "passive"))
    )
    (net (code "81") (name "/TEMP+_1") (class "Default")
      (node (ref "J43") (pin "+") (pinfunction "+_+") (pintype "passive"))
    )
    (net (code "82") (name "/TEMP+_2") (class "Default")
      (node (ref "J44") (pin "+") (pinfunction "+_+") (pintype "passive"))
    )
    (net (code "83") (name "/TEMP+_3") (class "Default")
      (node (ref "J45") (pin "+") (pinfunction "+_+") (pintype "passive"))
    )
    (net (code "84") (name "/TEMP+_4") (class "Default")
      (node (ref "J46") (pin "+") (pinfunction "+_+") (pintype "passive"))
    )
    (net (code "85") (name "/TEMP+_5") (class "Default")
      (node (ref "J47") (pin "+") (pinfunction "+_+") (pintype "passive"))
    )
    (net (code "86") (name "/TEMP+_6") (class "Default")
      (node (ref "J48") (pin "+") (pinfunction "+_+") (pintype "passive"))
    )
    (net (code "87") (name "/TEMP+_7") (class "Default")
      (node (ref "J49") (pin "+") (pinfunction "+_+") (pintype "passive"))
    )
    (net (code "88") (name "/TEMP+_8") (class "Default")
      (node (ref "J50") (pin "+") (pinfunction "+_+") (pintype "passive"))
    )
    (net (code "89") (name "/TEMP+_9") (class "Default")
      (node (ref "J51") (pin "+") (pinfunction "+_+") (pintype "passive"))
    )
    (net (code "90") (name "/TEMP+_10") (class "Default")
      (node (ref "J52") (pin "+") (pinfunction "+_+") (pintype "passive"))
    )
    (net (code "91") (name "/TEMP+_11") (class "Default")
      (node (ref "J53") (pin "+") (pinfunction "+_+") (pintype "passive"))
    )
    (net (code "92") (name "/TEMP-_0") (class "Default")
      (node (ref "J42") (pin "K") (pinfunction "K_K") (pintype "passive"))
    )
    (net (code "93") (name "/TEMP-_1") (class "Default")
      (node (ref "J43") (pin "K") (pinfunction "K_K") (pintype "passive"))
    )
    (net (code "94") (name "/TEMP-_2") (class "Default")
      (node (ref "J44") (pin "K") (pinfunction "K_K") (pintype "passive"))
    )
    (net (code "95") (name "/TEMP-_3") (class "Default")
      (node (ref "J45") (pin "K") (pinfunction "K_K") (pintype "passive"))
    )
    (net (code "96") (name "/TEMP-_4") (class "Default")
      (node (ref "J46") (pin "K") (pinfunction "K_K") (pintype "passive"))
    )
    (net (code "97") (name "/TEMP-_5") (class "Default")
      (node (ref "J47") (pin "K") (pinfunction "K_K") (pintype "passive"))
    )
    (net (code "98") (name "/TEMP-_6") (class "Default")
      (node (ref "J48") (pin "K") (pinfunction "K_K") (pintype "passive"))
    )
    (net (code "99") (name "/TEMP-_7") (class "Default")
      (node (ref "J49") (pin "K") (pinfunction "K_K") (pintype "passive"))
    )
    (net (code "100") (name "/TEMP-_8") (class "Default")
      (node (ref "J50") (pin "K") (pinfunction "K_K") (pintype "passive"))
    )
    (net (code "101") (name "/TEMP-_9") (class "Default")
      (node (ref "J51") (pin "K") (pinfunction "K_K") (pintype "passive"))
    )
    (net (code "102") (name "/TEMP-_10") (class "Default")
      (node (ref "J52") (pin "K") (pinfunction "K_K") (pintype "passive"))
    )
    (net (code "103") (name "/TEMP-_11") (class "Default")
      (node (ref "J53") (pin "K") (pinfunction "K_K") (pintype "passive"))
    )
    (net (code "112") (name "120VAC") (class "Default")
      (node (ref "U1") (pin "2") (pinfunction "2_2") (pintype "passive"))
    )
    (net (code "113") (name "120VAC_RETURN") (class "Default")
      (node (ref "J1") (pin "N") (pinfunction "N_N") (pintype "passive"))
      (node (ref "J10") (pin "1") (pinfunction "1_1") (pintype "passive"))
      (node (ref "J11") (pin "1") (pinfunction "1_1") (pintype "passive"))
      (node (ref "J12") (pin "1") (pinfunction "1_1") (pintype "passive"))
      (node (ref "J13") (pin "1") (pinfunction "1_1") (pintype "passive"))
      (node (ref "J14") (pin "1") (pinfunction "1_1") (pintype "passive"))
      (node (ref "J15") (pin "1") (pinfunction "1_1") (pintype "passive"))
      (node (ref "J16") (pin "1") (pinfunction "1_1") (pintype "passive"))
      (node (ref "J17") (pin "1") (pinfunction "1_1") (pintype "passive"))
      (node (ref "J30") (pin "1") (pinfunction "1_1") (pintype "passive"))
      (node (ref "J31") (pin "1") (pinfunction "1_1") (pintype "passive"))
      (node (ref "J32") (pin "1") (pinfunction "1_1") (pintype "passive"))
      (node (ref "J33") (pin "1") (pinfunction "1_1") (pintype "passive"))
      (node (ref "J34") (pin "1") (pinfunction "1_1") (pintype "passive"))
      (node (ref "J35") (pin "1") (pinfunction "1_1") (pintype "passive"))
      (node (ref "J36") (pin "1") (pinfunction "1_1") (pintype "passive"))
      (node (ref "J37") (pin "1") (pinfunction "1_1") (pintype "passive"))
      (node (ref "J38") (pin "1") (pinfunction "1_1") (pintype "passive"))
      (node (ref "J39") (pin "1") (pinfunction "1_1") (pintype "passive"))
      (node (ref "J40") (pin "1") (pinfunction "1_1") (pintype "passive"))
      (node (ref "J41") (pin "1") (pinfunction "1_1") (pintype "passive"))
    )
    (net (code "114") (name "GND") (class "Default")
      (node (ref "J54") (pin "1-3") (pinfunction "1-3_1-3") (pintype "passive"))
      (node (ref "J54") (pin "1-4") (pinfunction "1-4_1-4") (pintype "passive"))
      (node (ref "J54") (pin "1-5") (pinfunction "1-5_1-5") (pintype "passive"))
      (node (ref "J54") (pin "1-7") (pinfunction "1-7_1-7") (pintype "passive"))
      (node (ref "J54") (pin "10-1") (pinfunction "10-1_10-1") (pintype "passive"))
      (node (ref "J54") (pin "10-3") (pinfunction "10-3_10-3") (pintype "passive"))
      (node (ref "J54") (pin "11-2") (pinfunction "11-2_11-2") (pintype "passive"))
      (node (ref "J54") (pin "11-4") (pinfunction "11-4_11-4") (pintype "passive"))
      (node (ref "J54") (pin "11-6") (pinfunction "11-6_11-6") (pintype "passive"))
      (node (ref "J54") (pin "11-8") (pinfunction "11-8_11-8") (pintype "passive"))
      (node (ref "J54") (pin "12-2") (pinfunction "12-2_12-2") (pintype "passive"))
      (node (ref "J54") (pin "12-4") (pinfunction "12-4_12-4") (pintype "passive"))
      (node (ref "J54") (pin "12-6") (pinfunction "12-6_12-6") (pintype "passive"))
      (node (ref "J54") (pin "12-8") (pinfunction "12-8_12-8") (pintype "passive"))
      (node (ref "J54") (pin "2-3") (pinfunction "2-3_2-3") (pintype "passive"))
      (node (ref "J54") (pin "2-4") (pinfunction "2-4_2-4") (pintype "passive"))
      (node (ref "J54") (pin "2-5") (pinfunction "2-5_2-5") (pintype "passive"))
      (node (ref "J54") (pin "2-7") (pinfunction "2-7_2-7") (pintype "passive"))
      (node (ref "J54") (pin "3-3") (pinfunction "3-3_3-3") (pintype "passive"))
      (node (ref "J54") (pin "3-4") (pinfunction "3-4_3-4") (pintype "passive"))
      (node (ref "J54") (pin "3-5") (pinfunction "3-5_3-5") (pintype "passive"))
      (node (ref "J54") (pin "3-7") (pinfunction "3-7_3-7") (pintype "passive"))
      (node (ref "J54") (pin "4-3") (pinfunction "4-3_4-3") (pintype "passive"))
      (node (ref "J54") (pin "4-4") (pinfunction "4-4_4-4") (pintype "passive"))
      (node (ref "J54") (pin "4-5") (pinfunction "4-5_4-5") (pintype "passive"))
      (node (ref "J54") (pin "4-7") (pinfunction "4-7_4-7") (pintype "passive"))
      (node (ref "J54") (pin "5-2") (pinfunction "5-2_5-2") (pintype "passive"))
      (node (ref "J54") (pin "5-4") (pinfunction "5-4_5-4") (pintype "passive"))
      (node (ref "J54") (pin "5-6") (pinfunction "5-6_5-6") (pintype "passive"))
      (node (ref "J54") (pin "5-8") (pinfunction "5-8_5-8") (pintype "passive"))
      (node (ref "J54") (pin "7-3") (pinfunction "7-3_7-3") (pintype "passive"))
      (node (ref "J54") (pin "7-4") (pinfunction "7-4_7-4") (pintype "passive"))
      (node (ref "J54") (pin "7-5") (pinfunction "7-5_7-5") (pintype "passive"))
      (node (ref "J54") (pin "7-7") (pinfunction "7-7_7-7") (pintype "passive"))
      (node (ref "J54") (pin "8-3") (pinfunction "8-3_8-3") (pintype "passive"))
      (node (ref "J54") (pin "8-4") (pinfunction "8-4_8-4") (pintype "passive"))
      (node (ref "J54") (pin "8-5") (pinfunction "8-5_8-5") (pintype "passive"))
      (node (ref "J54") (pin "8-7") (pinfunction "8-7_8-7") (pintype "passive"))
      (node (ref "J54") (pin "9-3") (pinfunction "9-3_9-3") (pintype "passive"))
      (node (ref "J54") (pin "9-4") (pinfunction "9-4_9-4") (pintype "passive"))
      (node (ref "J54") (pin "9-5") (pinfunction "9-5_9-5") (pintype "passive"))
      (node (ref "J54") (pin "9-7") (pinfunction "9-7_9-7") (pintype "passive"))
    )
    (net (code "115") (name "MFC_+15v") (class "Default")
      (node (ref "J54") (pin "1-1") (pinfunction "1-1_1-1") (pintype "passive"))
      (node (ref "J54") (pin "2-1") (pinfunction "2-1_2-1") (pintype "passive"))
      (node (ref "J54") (pin "3-1") (pinfunction "3-1_3-1") (pintype "passive"))
      (node (ref "J54") (pin "4-1") (pinfunction "4-1_4-1") (pintype "passive"))
      (node (ref "J54") (pin "7-1") (pinfunction "7-1_7-1") (pintype "passive"))
      (node (ref "J54") (pin "8-1") (pinfunction "8-1_8-1") (pintype "passive"))
      (node (ref "J54") (pin "9-1") (pinfunction "9-1_9-1") (pintype "passive"))
    )
    (net (code "116") (name "MFC_-15v") (class "Default")
      (node (ref "J54") (pin "1-2") (pinfunction "1-2_1-2") (pintype "passive"))
      (node (ref "J54") (pin "2-2") (pinfunction "2-2_2-2") (pintype "passive"))
      (node (ref "J54") (pin "3-2") (pinfunction "3-2_3-2") (pintype "passive"))
      (node (ref "J54") (pin "4-2") (pinfunction "4-2_4-2") (pintype "passive"))
      (node (ref "J54") (pin "7-2") (pinfunction "7-2_7-2") (pintype "passive"))
      (node (ref "J54") (pin "8-2") (pinfunction "8-2_8-2") (pintype "passive"))
      (node (ref "J54") (pin "9-2") (pinfunction "9-2_9-2") (pintype "passive"))
    )
    (net (code "117") (name "Net-(J1-PadL)") (class "Default")
      (node (ref "J1") (pin "L") (pinfunction "L_L") (pintype "passive"))
      (node (ref "U1") (pin "1") (pinfunction "1_1") (pintype "passive"))
    )
    (net (code "118") (name "Net-(U43-GND)") (class "Default")
      (node (ref "U43") (pin "14") (pinfunction "14_14") (pintype "passive"))
      (node (ref "U43") (pin "3") (pinfunction "GND_3") (pintype "passive"))
    )
    (net (code "119") (name "Net-(U43-Pad15)") (class "Default")
      (node (ref "U43") (pin "15") (pinfunction "15_15") (pintype "passive"))
      (node (ref "U43") (pin "2") (pinfunction "SW_2") (pintype "passive"))
    )
    (net (code "120") (name "Net-(U43-Pad16)") (class "Default")
      (node (ref "U43") (pin "1") (pinfunction "SW_1") (pintype "passive"))
      (node (ref "U43") (pin "16") (pinfunction "16_16") (pintype "passive"))
    )
    (net (code "121") (name "Net-(U43-SCK)") (class "Default")
      (node (ref "U43") (pin "10") (pinfunction "10_10") (pintype "passive"))
      (node (ref "U43") (pin "7") (pinfunction "SCK_7") (pintype "passive"))
    )
    (net (code "122") (name "Net-(U43-SDI)") (class "Default")
      (node (ref "U43") (pin "11") (pinfunction "11_11") (pintype "passive"))
      (node (ref "U43") (pin "6") (pinfunction "SDI_6") (pintype "passive"))
    )
    (net (code "123") (name "Net-(U43-SDO)") (class "Default")
      (node (ref "U43") (pin "12") (pinfunction "12_12") (pintype "passive"))
      (node (ref "U43") (pin "5") (pinfunction "SDO_5") (pintype "passive"))
    )
    (net (code "124") (name "Net-(U43-VDD)") (class "Default")
      (node (ref "U43") (pin "13") (pinfunction "13_13") (pintype "passive"))
      (node (ref "U43") (pin "4") (pinfunction "VDD_4") (pintype "passive"))
    )
    (net (code "125") (name "Net-(U43-~{SS})") (class "Default")
      (node (ref "U43") (pin "8") (pinfunction "~{SS}_8") (pintype "passive"))
      (node (ref "U43") (pin "9") (pinfunction "9_9") (pintype "passive"))
    )
    (net (code "126") (name "unconnected-(J1-G-PadE)") (class "Default")
      (node (ref "J1") (pin "E") (pinfunction "G_E") (pintype "passive"))
    )
    (net (code "127") (name "unconnected-(J54-Pad6-5)") (class "Default")
      (node (ref "J54") (pin "6-5") (pinfunction "6-5_6-5") (pintype "passive"))
    )
    (net (code "128") (name "unconnected-(J54-Pad6-6)") (class "Default")
      (node (ref "J54") (pin "6-6") (pinfunction "6-6_6-6") (pintype "passive"))
    )
    (net (code "129") (name "unconnected-(J54-Pad6-7)") (class "Default")
      (node (ref "J54") (pin "6-7") (pinfunction "6-7_6-7") (pintype "passive"))
    )
    (net (code "130") (name "unconnected-(J54-Pad6-8)") (class "Default")
      (node (ref "J54") (pin "6-8") (pinfunction "6-8_6-8") (pintype "passive"))
    )
    (net (code "131") (name "unconnected-(J54-Pad10-5)") (class "Default")
      (node (ref "J54") (pin "10-5") (pinfunction "10-5_10-5") (pintype "passive"))
    )
    (net (code "132") (name "unconnected-(J54-Pad10-6)") (class "Default")
      (node (ref "J54") (pin "10-6") (pinfunction "10-6_10-6") (pintype "passive"))
    )
    (net (code "133") (name "unconnected-(J54-Pad10-7)") (class "Default")
      (node (ref "J54") (pin "10-7") (pinfunction "10-7_10-7") (pintype "passive"))
    )
    (net (code "134") (name "unconnected-(J54-Pad10-8)") (class "Default")
      (node (ref "J54") (pin "10-8") (pinfunction "10-8_10-8") (pintype "passive"))
    )
    (net (code "135") (name "unconnected-(U43-Pad20)") (class "Default")
      (node (ref "U43") (pin "20") (pinfunction "20_20") (pintype "passive"))
    )
    (net (code "136") (name "unconnected-(U43-Pad21)") (class "Default")
      (node (ref "U43") (pin "21") (pinfunction "21_21") (pintype "passive"))
    )
    (net (code "137") (name "unconnected-(U43-Pad22)") (class "Default")
      (node (ref "U43") (pin "22") (pinfunction "22_22") (pintype "passive"))
    )
  )
)
